# HC-SR04_v2_SCH.net
KiCad netlist of a schematic drawn in Altium Designer
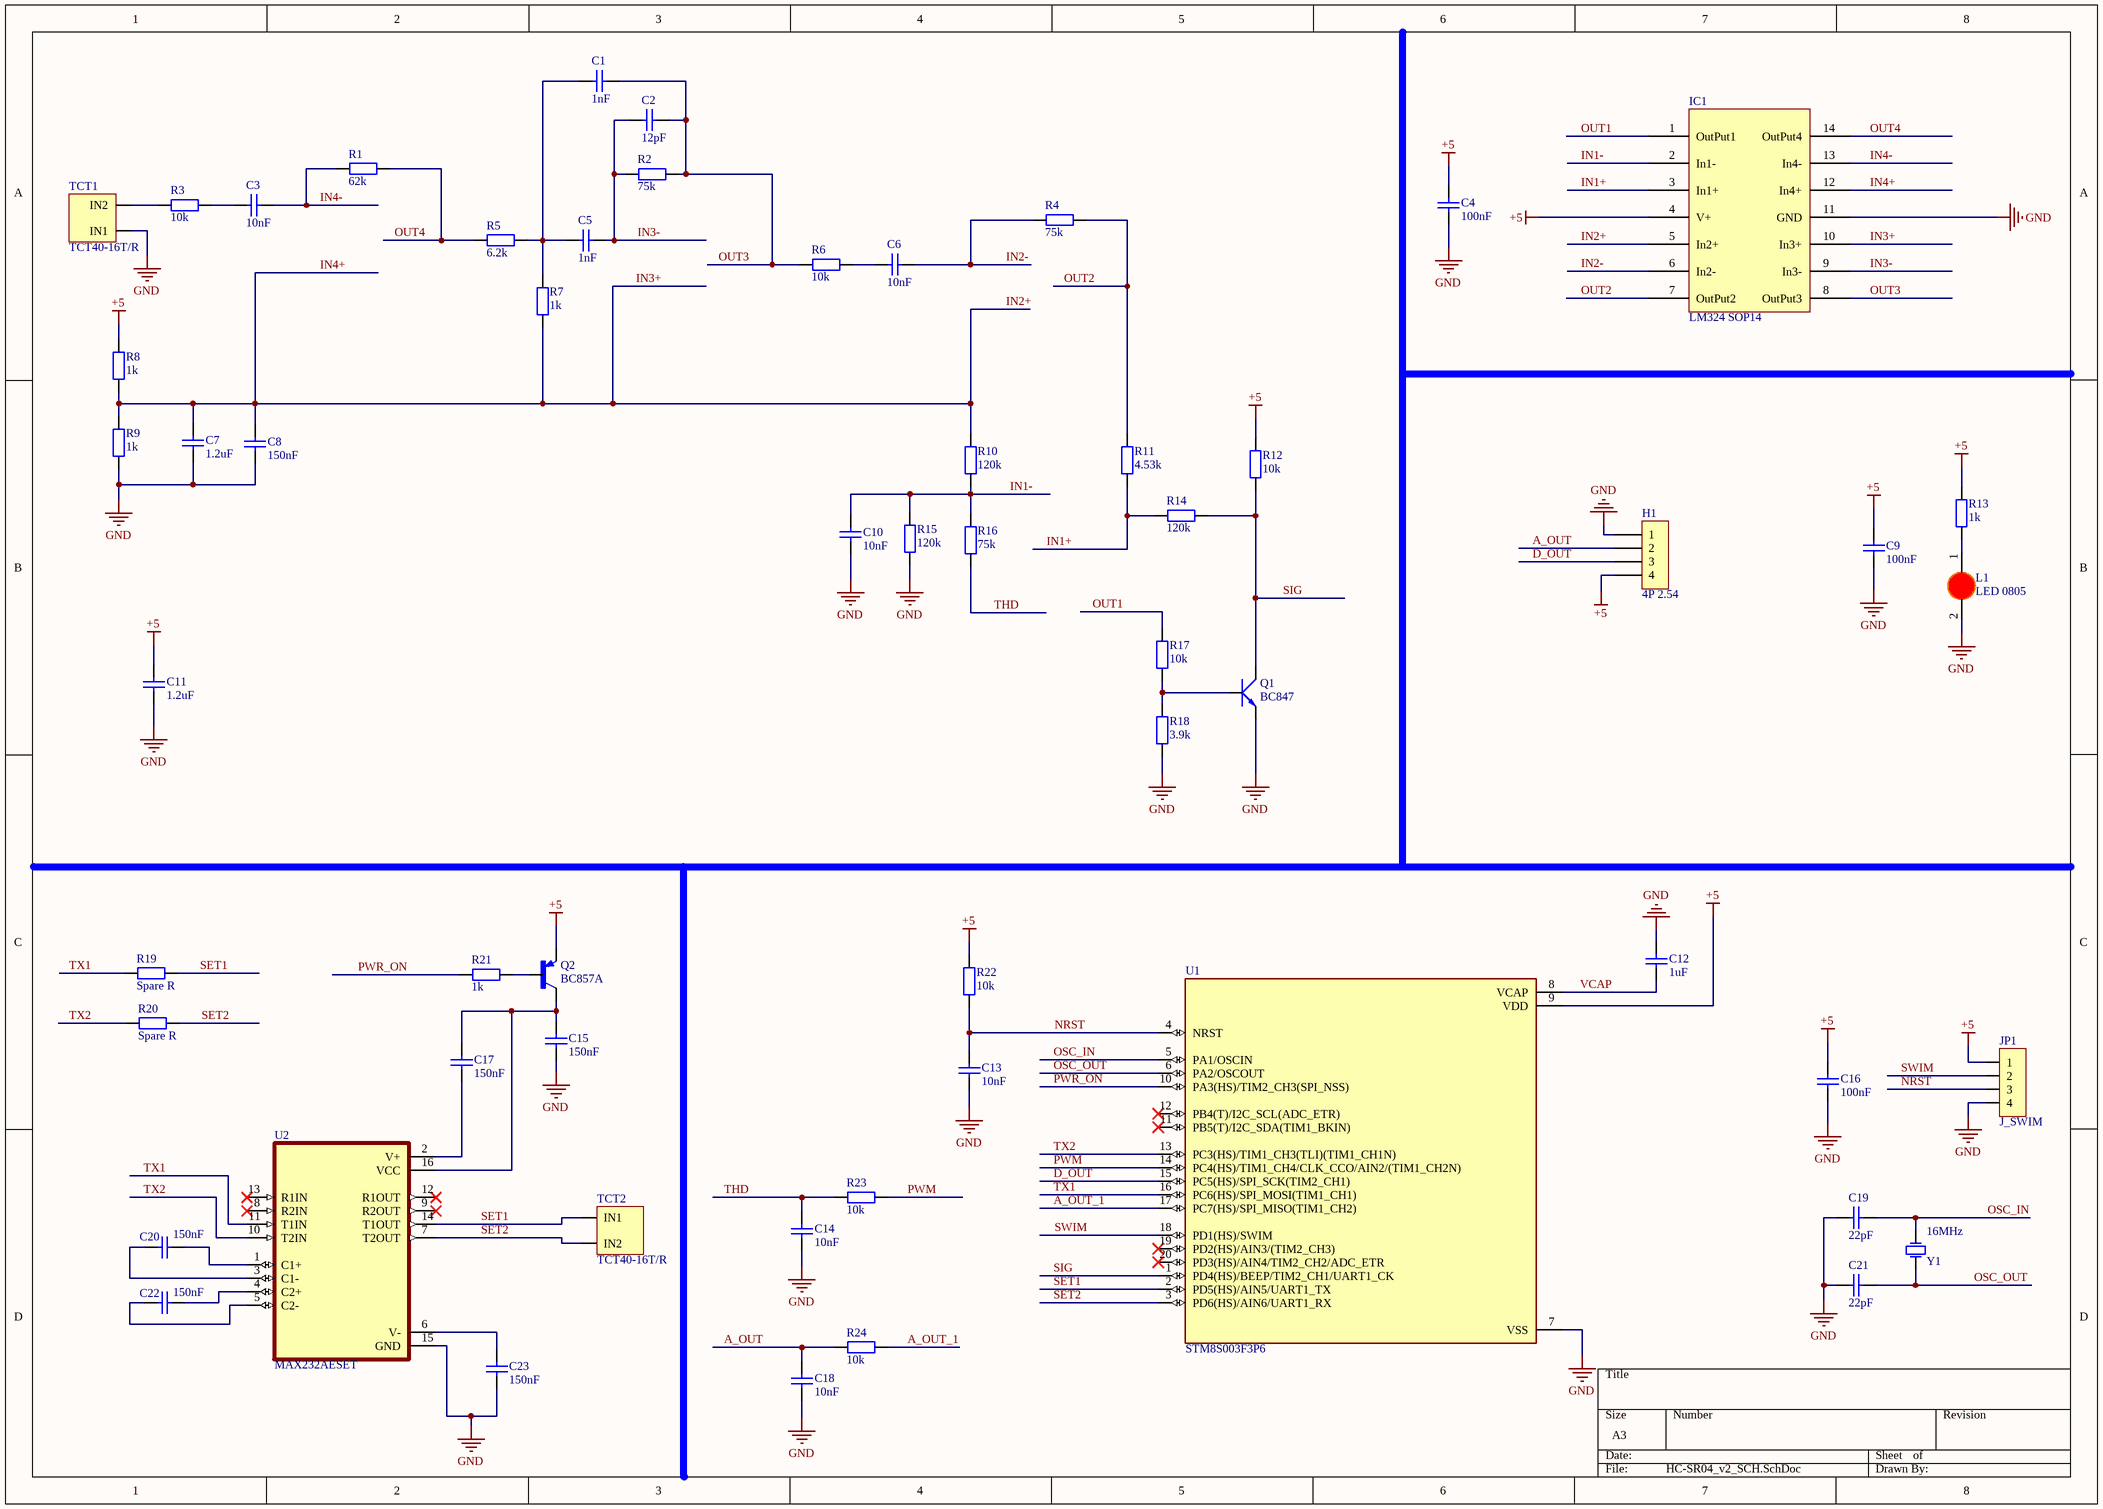
[diagram p0: HC-SR04_v2_SCH.SchDoc]

(export (version "E")
  (design (tool "Eeschema 10.0.6"))
  (components
    (comp (ref "C1")
      (value "1nF")
      (footprint "tu 0603")
      (description "Dán")
      (libsource (lib "namnt_Lib") (part "Tu 0603 102 50V 10%"))
    )
    (comp (ref "C2")
      (value "12pF")
      (footprint "tu 0603")
      (description "Dán")
      (libsource (lib "namnt_Lib") (part "Tu 0603 102 50V 10%"))
    )
    (comp (ref "C3")
      (value "10nF")
      (footprint "tu 0603")
      (description "Dán")
      (libsource (lib "namnt_Lib") (part "Tu 0603 103 50V 10%"))
    )
    (comp (ref "C4")
      (value "100nF")
      (footprint "tu 0603")
      (description "Dán")
      (libsource (lib "namnt_Lib") (part "Tu 0603 102 50V 10%"))
    )
    (comp (ref "C5")
      (value "1nF")
      (footprint "tu 0603")
      (description "Dán")
      (libsource (lib "namnt_Lib") (part "Tu 0603 102 50V 10%"))
    )
    (comp (ref "C6")
      (value "10nF")
      (footprint "tu 0603")
      (description "Dán")
      (libsource (lib "namnt_Lib") (part "Tu 0603 102 50V 10%"))
    )
    (comp (ref "C7")
      (value "1.2uF")
      (footprint "tu 0603")
      (description "Dán")
      (libsource (lib "namnt_Lib") (part "Tu 0603 104 50V 10%"))
    )
    (comp (ref "C8")
      (value "150nF")
      (footprint "tu 0603")
      (description "Dán")
      (libsource (lib "namnt_Lib") (part "Tu 0603 104 50V 10%"))
    )
    (comp (ref "C9")
      (value "100nF")
      (footprint "tu 0603")
      (description "Dán")
      (libsource (lib "namnt_Lib") (part "Tu 0603 102 50V 10%"))
    )
    (comp (ref "C10")
      (value "10nF")
      (footprint "tu 0603")
      (description "Dán")
      (libsource (lib "namnt_Lib") (part "Tu 0603 102 50V 10%"))
    )
    (comp (ref "C11")
      (value "1.2uF")
      (footprint "tu 0603")
      (description "Dán")
      (libsource (lib "namnt_Lib") (part "Tu 0603 102 50V 10%"))
    )
    (comp (ref "C12")
      (value "1uF")
      (footprint "tu 0603")
      (description "Dán")
      (libsource (lib "namnt_Lib") (part "Tu 0603 102 50V 10%"))
    )
    (comp (ref "C13")
      (value "10nF")
      (footprint "tu 0603")
      (description "Dán")
      (libsource (lib "namnt_Lib") (part "Tu 0603 102 50V 10%"))
    )
    (comp (ref "C14")
      (value "10nF")
      (footprint "tu 0603")
      (description "Dán")
      (libsource (lib "namnt_Lib") (part "Tu 0603 102 50V 10%"))
    )
    (comp (ref "C15")
      (value "150nF")
      (footprint "tu 0603")
      (description "Dán")
      (libsource (lib "namnt_Lib") (part "Tu 0603 102 50V 10%"))
    )
    (comp (ref "C16")
      (value "100nF")
      (footprint "tu 0603")
      (description "Dán")
      (libsource (lib "namnt_Lib") (part "Tu 0603 102 50V 10%"))
    )
    (comp (ref "C17")
      (value "150nF")
      (footprint "tu 0603")
      (description "Dán")
      (libsource (lib "namnt_Lib") (part "Tu 0603 102 50V 10%"))
    )
    (comp (ref "C18")
      (value "10nF")
      (footprint "tu 0603")
      (description "Dán")
      (libsource (lib "namnt_Lib") (part "Tu 0603 102 50V 10%"))
    )
    (comp (ref "C19")
      (value "22pF")
      (footprint "tu 0603")
      (description "Dán")
      (libsource (lib "namnt_Lib") (part "Tu 0603 102 50V 10%"))
    )
    (comp (ref "C20")
      (value "150nF")
      (footprint "tu 0603")
      (description "Dán")
      (libsource (lib "namnt_Lib") (part "Tu 0603 102 50V 10%"))
    )
    (comp (ref "C21")
      (value "22pF")
      (footprint "tu 0603")
      (description "Dán")
      (libsource (lib "namnt_Lib") (part "Tu 0603 102 50V 10%"))
    )
    (comp (ref "C22")
      (value "150nF")
      (footprint "tu 0603")
      (description "Dán")
      (libsource (lib "namnt_Lib") (part "Tu 0603 102 50V 10%"))
    )
    (comp (ref "C23")
      (value "150nF")
      (footprint "tu 0603")
      (description "Dán")
      (libsource (lib "namnt_Lib") (part "Tu 0603 102 50V 10%"))
    )
    (comp (ref "H1")
      (value "4P 2.54")
      (footprint "Header 4P DC 2.54")
      (description "Cắm")
      (libsource (lib "namnt_Lib") (part "Header 4P 2.54 Duc Cong"))
    )
    (comp (ref "IC1")
      (value "LM324 SOP14")
      (footprint "sop 14")
      (description "Dán")
      (libsource (lib "namnt_Lib") (part "LM324 SOP14"))
    )
    (comp (ref "JP1")
      (value "J_SWIM")
      (footprint "JP 1x4 DT")
      (description "Cắm")
      (libsource (lib "namnt_Lib") (part "JP 1x4 2.54 Duc Thang"))
    )
    (comp (ref "L1")
      (value "LED 0805")
      (footprint "LED-0805-Red")
      (description "Dán")
      (libsource (lib "namnt_Lib") (part "LED 0805 Do"))
    )
    (comp (ref "Q1")
      (value "BC847")
      (footprint "SOT-23")
      (description "SOT-23")
      (libsource (lib "namnt_Lib") (part "Trans BC817"))
    )
    (comp (ref "Q2")
      (value "BC857A")
      (footprint "TRANS_BC857A_RFG")
      (description "SOT-23, 200mW, PNP Bipolar Transistor")
      (fields (field (name "MF") "Taiwan Semiconductor") (field (name "MP") "BC857A RFG"))
      (libsource (lib "namnt_Lib") (part "BC857A_RFG"))
    )
    (comp (ref "R1")
      (value "62k")
      (footprint "tro smd 0603")
      (description "Dán")
      (libsource (lib "namnt_Lib") (part "Tro 0603 1% 1k"))
    )
    (comp (ref "R2")
      (value "75k")
      (footprint "tro smd 0603")
      (description "Dán")
      (libsource (lib "namnt_Lib") (part "Tro 0603 1% 1k"))
    )
    (comp (ref "R3")
      (value "10k")
      (footprint "tro smd 0603")
      (description "Dán")
      (libsource (lib "namnt_Lib") (part "Tro 0603 1% 10k"))
    )
    (comp (ref "R4")
      (value "75k")
      (footprint "tro smd 0603")
      (description "Dán")
      (libsource (lib "namnt_Lib") (part "Tro 0603 1% 1k"))
    )
    (comp (ref "R5")
      (value "6.2k")
      (footprint "tro smd 0603")
      (description "Dán")
      (libsource (lib "namnt_Lib") (part "Tro 0603 1% 1k"))
    )
    (comp (ref "R6")
      (value "10k")
      (footprint "tro smd 0603")
      (description "Dán")
      (libsource (lib "namnt_Lib") (part "Tro 0603 1% 1k"))
    )
    (comp (ref "R7")
      (value "1k")
      (footprint "tro smd 0603")
      (description "Dán")
      (libsource (lib "namnt_Lib") (part "Tro 0603 1% 1k"))
    )
    (comp (ref "R8")
      (value "1k")
      (footprint "tro smd 0603")
      (description "Dán")
      (libsource (lib "namnt_Lib") (part "Tro 0603 1% 1k"))
    )
    (comp (ref "R9")
      (value "1k")
      (footprint "tro smd 0603")
      (description "Dán")
      (libsource (lib "namnt_Lib") (part "Tro 0603 1% 1k"))
    )
    (comp (ref "R10")
      (value "120k")
      (footprint "tro smd 0603")
      (description "Dán")
      (libsource (lib "namnt_Lib") (part "Tro 0603 1% 1k"))
    )
    (comp (ref "R11")
      (value "4.53k")
      (footprint "tro smd 0603")
      (description "Dán")
      (libsource (lib "namnt_Lib") (part "Tro 0603 1% 1k"))
    )
    (comp (ref "R12")
      (value "10k")
      (footprint "tro smd 0603")
      (description "Dán")
      (libsource (lib "namnt_Lib") (part "Tro 0603 1% 1k"))
    )
    (comp (ref "R13")
      (value "1k")
      (footprint "tro smd 0603")
      (description "Dán")
      (libsource (lib "namnt_Lib") (part "Tro 0603 1% 1k"))
    )
    (comp (ref "R14")
      (value "120k")
      (footprint "tro smd 0603")
      (description "Dán")
      (libsource (lib "namnt_Lib") (part "Tro 0603 1% 1k"))
    )
    (comp (ref "R15")
      (value "120k")
      (footprint "tro smd 0603")
      (description "Dán")
      (libsource (lib "namnt_Lib") (part "Tro 0603 1% 1k"))
    )
    (comp (ref "R16")
      (value "75k")
      (footprint "tro smd 0603")
      (description "Dán")
      (libsource (lib "namnt_Lib") (part "Tro 0603 1% 1k"))
    )
    (comp (ref "R17")
      (value "10k")
      (footprint "tro smd 0603")
      (description "Dán")
      (libsource (lib "namnt_Lib") (part "Tro 0603 1% 1k"))
    )
    (comp (ref "R18")
      (value "3.9k")
      (footprint "tro smd 0603")
      (description "Dán")
      (libsource (lib "namnt_Lib") (part "Tro 0603 1% 1k"))
    )
    (comp (ref "R19")
      (value "Spare R")
      (footprint "tro smd 0603")
      (description "Dán")
      (libsource (lib "namnt_Lib") (part "Tro 0603 1% 1k"))
    )
    (comp (ref "R20")
      (value "Spare R")
      (footprint "tro smd 0603")
      (description "Dán")
      (libsource (lib "namnt_Lib") (part "Tro 0603 1% 1k"))
    )
    (comp (ref "R21")
      (value "1k")
      (footprint "tro smd 0603")
      (description "Dán")
      (libsource (lib "namnt_Lib") (part "Tro 0603 1% 1k"))
    )
    (comp (ref "R22")
      (value "10k")
      (footprint "tro smd 0603")
      (description "Dán")
      (libsource (lib "namnt_Lib") (part "Tro 0603 1% 1k"))
    )
    (comp (ref "R23")
      (value "10k")
      (footprint "tro smd 0603")
      (description "Dán")
      (libsource (lib "namnt_Lib") (part "Tro 0603 1% 1k"))
    )
    (comp (ref "R24")
      (value "10k")
      (footprint "tro smd 0603")
      (description "Dán")
      (libsource (lib "namnt_Lib") (part "Tro 0603 1% 1k"))
    )
    (comp (ref "TCT1")
      (value "TCT40-16T/R")
      (footprint "TCT40")
      (description "Piezoelectric Ceramic Ultrasonic Sensor")
      (libsource (lib "") (part "TCT40-16T/R_1"))
    )
    (comp (ref "TCT2")
      (value "TCT40-16T/R")
      (footprint "TCT40")
      (description "Piezoelectric Ceramic Ultrasonic Sensor")
      (libsource (lib "namnt_Lib") (part "TCT40-16T/R"))
    )
    (comp (ref "U1")
      (value "STM8S003F3P6")
      (footprint "SOP65P640X120-20N")
      (description "STM8 series Microcontroller IC 8-Bit 16MHz 8KB (8K x 8) FLASH 20-TSSOP")
      (fields (field (name "MF") "STMicroelectronics"))
      (libsource (lib "namnt_Lib") (part "STM8S003F3P6"))
    )
    (comp (ref "U2")
      (value "MAX232AESET")
      (footprint "SOIC127P600X175-16N")
      (description "Dual Transmitter/Receiver RS-232 16-Pin SOIC N Tube")
      (fields (field (name "MF") "Analog Devices") (field (name "MP") "MAX232AESE+"))
      (libsource (lib "namnt_Lib") (part "MAX232AESET"))
    )
    (comp (ref "Y1")
      (value "16MHz")
      (footprint "THACH ANH DAN 3215")
      (description "C700805")
      (libsource (lib "namnt_Lib") (part "Thach Anh SMD 3225"))
    )
  )
  (nets
    (net (code "1") (name "+5") (class "Default")
      (node (ref "C11") (pin "1") (pinfunction "1_1") (pintype "passive"))
      (node (ref "C16") (pin "1") (pinfunction "1_1") (pintype "passive"))
      (node (ref "C4") (pin "1") (pinfunction "1_1") (pintype "passive"))
      (node (ref "C9") (pin "1") (pinfunction "1_1") (pintype "passive"))
      (node (ref "H1") (pin "4") (pinfunction "4_4") (pintype "passive"))
      (node (ref "IC1") (pin "4") (pinfunction "V+_4") (pintype "passive"))
      (node (ref "JP1") (pin "1") (pinfunction "1_1") (pintype "passive"))
      (node (ref "Q2") (pin "2") (pinfunction "E_2") (pintype "passive"))
      (node (ref "R12") (pin "2") (pinfunction "2_2") (pintype "passive"))
      (node (ref "R13") (pin "2") (pinfunction "2_2") (pintype "passive"))
      (node (ref "R22") (pin "1") (pinfunction "1_1") (pintype "passive"))
      (node (ref "R8") (pin "2") (pinfunction "2_2") (pintype "passive"))
      (node (ref "U1") (pin "9") (pinfunction "VDD_9") (pintype "power_in"))
    )
    (net (code "2") (name "/A_OUT") (class "Default")
      (node (ref "C18") (pin "1") (pinfunction "1_1") (pintype "passive"))
      (node (ref "H1") (pin "2") (pinfunction "2_2") (pintype "passive"))
      (node (ref "R24") (pin "2") (pinfunction "2_2") (pintype "passive"))
    )
    (net (code "3") (name "/A_OUT_1") (class "Default")
      (node (ref "R24") (pin "1") (pinfunction "1_1") (pintype "passive"))
      (node (ref "U1") (pin "17") (pinfunction "PC7(HS)/SPI_MISO(TIM1_CH2)_17") (pintype "bidirectional"))
    )
    (net (code "4") (name "/D_OUT") (class "Default")
      (node (ref "H1") (pin "3") (pinfunction "3_3") (pintype "passive"))
      (node (ref "U1") (pin "15") (pinfunction "PC5(HS)/SPI_SCK(TIM2_CH1)_15") (pintype "bidirectional"))
    )
    (net (code "5") (name "/IN1+") (class "Default")
      (node (ref "IC1") (pin "3") (pinfunction "In1+_3") (pintype "passive"))
      (node (ref "R11") (pin "2") (pinfunction "2_2") (pintype "passive"))
      (node (ref "R14") (pin "1") (pinfunction "1_1") (pintype "passive"))
    )
    (net (code "6") (name "/IN1-") (class "Default")
      (node (ref "C10") (pin "1") (pinfunction "1_1") (pintype "passive"))
      (node (ref "IC1") (pin "2") (pinfunction "In1-_2") (pintype "passive"))
      (node (ref "R10") (pin "2") (pinfunction "2_2") (pintype "passive"))
      (node (ref "R15") (pin "2") (pinfunction "2_2") (pintype "passive"))
      (node (ref "R16") (pin "2") (pinfunction "2_2") (pintype "passive"))
    )
    (net (code "7") (name "/IN2+") (class "Default")
      (node (ref "C7") (pin "1") (pinfunction "1_1") (pintype "passive"))
      (node (ref "C8") (pin "1") (pinfunction "1_1") (pintype "passive"))
      (node (ref "IC1") (pin "10") (pinfunction "In3+_10") (pintype "passive"))
      (node (ref "IC1") (pin "12") (pinfunction "In4+_12") (pintype "passive"))
      (node (ref "IC1") (pin "5") (pinfunction "In2+_5") (pintype "passive"))
      (node (ref "R10") (pin "1") (pinfunction "1_1") (pintype "passive"))
      (node (ref "R7") (pin "2") (pinfunction "2_2") (pintype "passive"))
      (node (ref "R8") (pin "1") (pinfunction "1_1") (pintype "passive"))
      (node (ref "R9") (pin "2") (pinfunction "2_2") (pintype "passive"))
    )
    (net (code "8") (name "/IN2-") (class "Default")
      (node (ref "C6") (pin "1") (pinfunction "1_1") (pintype "passive"))
      (node (ref "IC1") (pin "6") (pinfunction "In2-_6") (pintype "passive"))
      (node (ref "R4") (pin "2") (pinfunction "2_2") (pintype "passive"))
    )
    (net (code "9") (name "/IN3-") (class "Default")
      (node (ref "C2") (pin "2") (pinfunction "2_2") (pintype "passive"))
      (node (ref "C5") (pin "1") (pinfunction "1_1") (pintype "passive"))
      (node (ref "IC1") (pin "9") (pinfunction "In3-_9") (pintype "passive"))
      (node (ref "R2") (pin "2") (pinfunction "2_2") (pintype "passive"))
    )
    (net (code "10") (name "/IN4-") (class "Default")
      (node (ref "C3") (pin "2") (pinfunction "2_2") (pintype "passive"))
      (node (ref "IC1") (pin "13") (pinfunction "In4-_13") (pintype "passive"))
      (node (ref "R1") (pin "2") (pinfunction "2_2") (pintype "passive"))
    )
    (net (code "11") (name "/NRST") (class "Default")
      (node (ref "C13") (pin "1") (pinfunction "1_1") (pintype "passive"))
      (node (ref "JP1") (pin "3") (pinfunction "3_3") (pintype "passive"))
      (node (ref "R22") (pin "2") (pinfunction "2_2") (pintype "passive"))
      (node (ref "U1") (pin "4") (pinfunction "NRST_4") (pintype "bidirectional"))
    )
    (net (code "12") (name "/OSC_IN") (class "Default")
      (node (ref "C19") (pin "2") (pinfunction "2_2") (pintype "passive"))
      (node (ref "U1") (pin "5") (pinfunction "PA1/OSCIN_5") (pintype "bidirectional"))
      (node (ref "Y1") (pin "2") (pinfunction "OSC2_2") (pintype "passive"))
    )
    (net (code "13") (name "/OSC_OUT") (class "Default")
      (node (ref "C21") (pin "2") (pinfunction "2_2") (pintype "passive"))
      (node (ref "U1") (pin "6") (pinfunction "PA2/OSCOUT_6") (pintype "bidirectional"))
      (node (ref "Y1") (pin "1") (pinfunction "OSC1_1") (pintype "passive"))
    )
    (net (code "14") (name "/OUT1") (class "Default")
      (node (ref "IC1") (pin "1") (pinfunction "OutPut1_1") (pintype "passive"))
      (node (ref "R17") (pin "2") (pinfunction "2_2") (pintype "passive"))
    )
    (net (code "15") (name "/OUT2") (class "Default")
      (node (ref "IC1") (pin "7") (pinfunction "OutPut2_7") (pintype "passive"))
      (node (ref "R11") (pin "1") (pinfunction "1_1") (pintype "passive"))
      (node (ref "R4") (pin "1") (pinfunction "1_1") (pintype "passive"))
    )
    (net (code "16") (name "/OUT3") (class "Default")
      (node (ref "C1") (pin "1") (pinfunction "1_1") (pintype "passive"))
      (node (ref "C2") (pin "1") (pinfunction "1_1") (pintype "passive"))
      (node (ref "IC1") (pin "8") (pinfunction "OutPut3_8") (pintype "passive"))
      (node (ref "R2") (pin "1") (pinfunction "1_1") (pintype "passive"))
      (node (ref "R6") (pin "2") (pinfunction "2_2") (pintype "passive"))
    )
    (net (code "17") (name "/OUT4") (class "Default")
      (node (ref "IC1") (pin "14") (pinfunction "OutPut4_14") (pintype "passive"))
      (node (ref "R1") (pin "1") (pinfunction "1_1") (pintype "passive"))
      (node (ref "R5") (pin "2") (pinfunction "2_2") (pintype "passive"))
    )
    (net (code "18") (name "/PWM") (class "Default")
      (node (ref "R23") (pin "1") (pinfunction "1_1") (pintype "passive"))
      (node (ref "U1") (pin "14") (pinfunction "PC4(HS)/TIM1_CH4/CLK_CCO/AIN2/(TIM1_CH2N)_14") (pintype "bidirectional"))
    )
    (net (code "19") (name "/PWR_ON") (class "Default")
      (node (ref "R21") (pin "2") (pinfunction "2_2") (pintype "passive"))
      (node (ref "U1") (pin "10") (pinfunction "PA3(HS)/TIM2_CH3(SPI_NSS)_10") (pintype "bidirectional"))
    )
    (net (code "20") (name "/SET1") (class "Default")
      (node (ref "R19") (pin "2") (pinfunction "2_2") (pintype "passive"))
      (node (ref "TCT2") (pin "1") (pinfunction "IN1_1") (pintype "passive"))
      (node (ref "U1") (pin "2") (pinfunction "PD5(HS)/AIN5/UART1_TX_2") (pintype "bidirectional"))
      (node (ref "U2") (pin "14") (pinfunction "T1OUT_14") (pintype "output"))
    )
    (net (code "21") (name "/SET2") (class "Default")
      (node (ref "R20") (pin "2") (pinfunction "2_2") (pintype "passive"))
      (node (ref "TCT2") (pin "2") (pinfunction "IN2_2") (pintype "passive"))
      (node (ref "U1") (pin "3") (pinfunction "PD6(HS)/AIN6/UART1_RX_3") (pintype "bidirectional"))
      (node (ref "U2") (pin "7") (pinfunction "T2OUT_7") (pintype "output"))
    )
    (net (code "22") (name "/SIG") (class "Default")
      (node (ref "Q1") (pin "3") (pinfunction "C_3") (pintype "passive"))
      (node (ref "R12") (pin "1") (pinfunction "1_1") (pintype "passive"))
      (node (ref "R14") (pin "2") (pinfunction "2_2") (pintype "passive"))
      (node (ref "U1") (pin "1") (pinfunction "PD4(HS)/BEEP/TIM2_CH1/UART1_CK_1") (pintype "bidirectional"))
    )
    (net (code "23") (name "/SWIM") (class "Default")
      (node (ref "JP1") (pin "2") (pinfunction "2_2") (pintype "passive"))
      (node (ref "U1") (pin "18") (pinfunction "PD1(HS)/SWIM_18") (pintype "bidirectional"))
    )
    (net (code "24") (name "/THD") (class "Default")
      (node (ref "C14") (pin "1") (pinfunction "1_1") (pintype "passive"))
      (node (ref "R16") (pin "1") (pinfunction "1_1") (pintype "passive"))
      (node (ref "R23") (pin "2") (pinfunction "2_2") (pintype "passive"))
    )
    (net (code "25") (name "/TX1") (class "Default")
      (node (ref "R19") (pin "1") (pinfunction "1_1") (pintype "passive"))
      (node (ref "U1") (pin "16") (pinfunction "PC6(HS)/SPI_MOSI(TIM1_CH1)_16") (pintype "bidirectional"))
      (node (ref "U2") (pin "11") (pinfunction "T1IN_11") (pintype "input"))
    )
    (net (code "26") (name "/TX2") (class "Default")
      (node (ref "R20") (pin "1") (pinfunction "1_1") (pintype "passive"))
      (node (ref "U1") (pin "13") (pinfunction "PC3(HS)/TIM1_CH3(TLI)(TIM1_CH1N)_13") (pintype "bidirectional"))
      (node (ref "U2") (pin "10") (pinfunction "T2IN_10") (pintype "input"))
    )
    (net (code "27") (name "/VCAP") (class "Default")
      (node (ref "C12") (pin "2") (pinfunction "2_2") (pintype "passive"))
      (node (ref "U1") (pin "8") (pinfunction "VCAP_8") (pintype "power_in"))
    )
    (net (code "28") (name "GND") (class "Default")
      (node (ref "C10") (pin "2") (pinfunction "2_2") (pintype "passive"))
      (node (ref "C11") (pin "2") (pinfunction "2_2") (pintype "passive"))
      (node (ref "C12") (pin "1") (pinfunction "1_1") (pintype "passive"))
      (node (ref "C13") (pin "2") (pinfunction "2_2") (pintype "passive"))
      (node (ref "C14") (pin "2") (pinfunction "2_2") (pintype "passive"))
      (node (ref "C15") (pin "2") (pinfunction "2_2") (pintype "passive"))
      (node (ref "C16") (pin "2") (pinfunction "2_2") (pintype "passive"))
      (node (ref "C18") (pin "2") (pinfunction "2_2") (pintype "passive"))
      (node (ref "C19") (pin "1") (pinfunction "1_1") (pintype "passive"))
      (node (ref "C21") (pin "1") (pinfunction "1_1") (pintype "passive"))
      (node (ref "C23") (pin "2") (pinfunction "2_2") (pintype "passive"))
      (node (ref "C4") (pin "2") (pinfunction "2_2") (pintype "passive"))
      (node (ref "C7") (pin "2") (pinfunction "2_2") (pintype "passive"))
      (node (ref "C8") (pin "2") (pinfunction "2_2") (pintype "passive"))
      (node (ref "C9") (pin "2") (pinfunction "2_2") (pintype "passive"))
      (node (ref "H1") (pin "1") (pinfunction "1_1") (pintype "passive"))
      (node (ref "IC1") (pin "11") (pinfunction "GND_11") (pintype "passive"))
      (node (ref "JP1") (pin "4") (pinfunction "4_4") (pintype "passive"))
      (node (ref "L1") (pin "2") (pinfunction "K_2") (pintype "passive"))
      (node (ref "Q1") (pin "2") (pinfunction "E_2") (pintype "passive"))
      (node (ref "R15") (pin "1") (pinfunction "1_1") (pintype "passive"))
      (node (ref "R18") (pin "1") (pinfunction "1_1") (pintype "passive"))
      (node (ref "R9") (pin "1") (pinfunction "1_1") (pintype "passive"))
      (node (ref "TCT1") (pin "1") (pinfunction "IN1_1") (pintype "passive"))
      (node (ref "U1") (pin "7") (pinfunction "VSS_7") (pintype "power_in"))
      (node (ref "U2") (pin "15") (pinfunction "GND_15") (pintype "power_in"))
    )
    (net (code "29") (name "Net-(C1-Pad2)") (class "Default")
      (node (ref "C1") (pin "2") (pinfunction "2_2") (pintype "passive"))
      (node (ref "C5") (pin "2") (pinfunction "2_2") (pintype "passive"))
      (node (ref "R5") (pin "1") (pinfunction "1_1") (pintype "passive"))
      (node (ref "R7") (pin "1") (pinfunction "1_1") (pintype "passive"))
    )
    (net (code "30") (name "Net-(C3-Pad1)") (class "Default")
      (node (ref "C3") (pin "1") (pinfunction "1_1") (pintype "passive"))
      (node (ref "R3") (pin "2") (pinfunction "2_2") (pintype "passive"))
    )
    (net (code "31") (name "Net-(C6-Pad2)") (class "Default")
      (node (ref "C6") (pin "2") (pinfunction "2_2") (pintype "passive"))
      (node (ref "R6") (pin "1") (pinfunction "1_1") (pintype "passive"))
    )
    (net (code "32") (name "Net-(L1-A)") (class "Default")
      (node (ref "L1") (pin "1") (pinfunction "A_1") (pintype "passive"))
      (node (ref "R13") (pin "1") (pinfunction "1_1") (pintype "passive"))
    )
    (net (code "33") (name "Net-(Q1-B)") (class "Default")
      (node (ref "Q1") (pin "1") (pinfunction "B_1") (pintype "passive"))
      (node (ref "R17") (pin "1") (pinfunction "1_1") (pintype "passive"))
      (node (ref "R18") (pin "2") (pinfunction "2_2") (pintype "passive"))
    )
    (net (code "34") (name "Net-(Q2-B)") (class "Default")
      (node (ref "Q2") (pin "1") (pinfunction "B_1") (pintype "passive"))
      (node (ref "R21") (pin "1") (pinfunction "1_1") (pintype "passive"))
    )
    (net (code "35") (name "Net-(Q2-C)") (class "Default")
      (node (ref "C15") (pin "1") (pinfunction "1_1") (pintype "passive"))
      (node (ref "C17") (pin "1") (pinfunction "1_1") (pintype "passive"))
      (node (ref "Q2") (pin "3") (pinfunction "C_3") (pintype "passive"))
      (node (ref "U2") (pin "16") (pinfunction "VCC_16") (pintype "power_in"))
    )
    (net (code "36") (name "Net-(TCT1-IN2)") (class "Default")
      (node (ref "R3") (pin "1") (pinfunction "1_1") (pintype "passive"))
      (node (ref "TCT1") (pin "2") (pinfunction "IN2_2") (pintype "passive"))
    )
    (net (code "37") (name "Net-(U2-C1+)") (class "Default")
      (node (ref "C20") (pin "2") (pinfunction "2_2") (pintype "passive"))
      (node (ref "U2") (pin "1") (pinfunction "C1+_1") (pintype "bidirectional"))
    )
    (net (code "38") (name "Net-(U2-C1-)") (class "Default")
      (node (ref "C20") (pin "1") (pinfunction "1_1") (pintype "passive"))
      (node (ref "U2") (pin "3") (pinfunction "C1-_3") (pintype "bidirectional"))
    )
    (net (code "39") (name "Net-(U2-C2+)") (class "Default")
      (node (ref "C22") (pin "2") (pinfunction "2_2") (pintype "passive"))
      (node (ref "U2") (pin "4") (pinfunction "C2+_4") (pintype "bidirectional"))
    )
    (net (code "40") (name "Net-(U2-C2-)") (class "Default")
      (node (ref "C22") (pin "1") (pinfunction "1_1") (pintype "passive"))
      (node (ref "U2") (pin "5") (pinfunction "C2-_5") (pintype "bidirectional"))
    )
    (net (code "41") (name "Net-(U2-V+)") (class "Default")
      (node (ref "C17") (pin "2") (pinfunction "2_2") (pintype "passive"))
      (node (ref "U2") (pin "2") (pinfunction "V+_2") (pintype "power_in"))
    )
    (net (code "42") (name "Net-(U2-V-)") (class "Default")
      (node (ref "C23") (pin "1") (pinfunction "1_1") (pintype "passive"))
      (node (ref "U2") (pin "6") (pinfunction "V-_6") (pintype "power_in"))
    )
    (net (code "43") (name "unconnected-(U1-PB4(T){slash}I2C_SCL(ADC_ETR)-Pad12)") (class "Default")
      (node (ref "U1") (pin "12") (pinfunction "PB4(T)/I2C_SCL(ADC_ETR)_12") (pintype "bidirectional+no_connect"))
    )
    (net (code "44") (name "unconnected-(U1-PB5(T){slash}I2C_SDA(TIM1_BKIN)-Pad11)") (class "Default")
      (node (ref "U1") (pin "11") (pinfunction "PB5(T)/I2C_SDA(TIM1_BKIN)_11") (pintype "bidirectional+no_connect"))
    )
    (net (code "45") (name "unconnected-(U1-PD2(HS){slash}AIN3{slash}(TIM2_CH3)-Pad19)") (class "Default")
      (node (ref "U1") (pin "19") (pinfunction "PD2(HS)/AIN3/(TIM2_CH3)_19") (pintype "bidirectional+no_connect"))
    )
    (net (code "46") (name "unconnected-(U1-PD3(HS){slash}AIN4{slash}TIM2_CH2{slash}ADC_ETR-Pad20)") (class "Default")
      (node (ref "U1") (pin "20") (pinfunction "PD3(HS)/AIN4/TIM2_CH2/ADC_ETR_20") (pintype "bidirectional+no_connect"))
    )
    (net (code "47") (name "unconnected-(U2-R1IN-Pad13)") (class "Default")
      (node (ref "U2") (pin "13") (pinfunction "R1IN_13") (pintype "input+no_connect"))
    )
    (net (code "48") (name "unconnected-(U2-R1OUT-Pad12)") (class "Default")
      (node (ref "U2") (pin "12") (pinfunction "R1OUT_12") (pintype "output+no_connect"))
    )
    (net (code "49") (name "unconnected-(U2-R2IN-Pad8)") (class "Default")
      (node (ref "U2") (pin "8") (pinfunction "R2IN_8") (pintype "input+no_connect"))
    )
    (net (code "50") (name "unconnected-(U2-R2OUT-Pad9)") (class "Default")
      (node (ref "U2") (pin "9") (pinfunction "R2OUT_9") (pintype "output+no_connect"))
    )
  )
)
